# LDR_MODULE.net
KiCad netlist of a schematic drawn in EAGLE
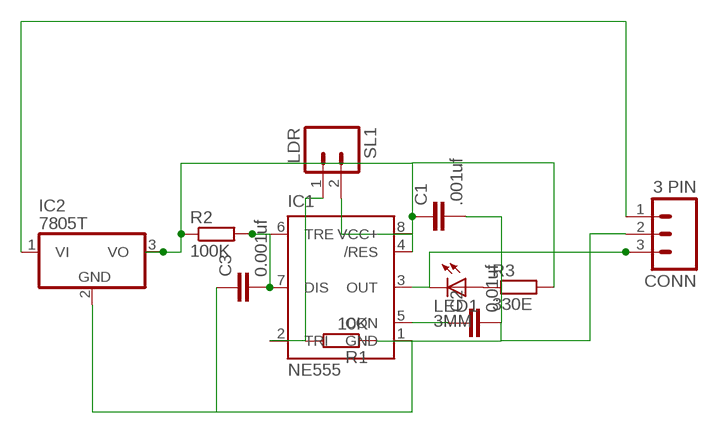
[diagram p0: schematic, sheet 1]

(export (version "E")
  (design (tool "Eeschema 10.0.6"))
  (components
    (comp (ref "C1")
      (value ".001uf")
      (footprint "eagle-import:C2.5-4")
      (libsource (lib "eagle-import") (part "C2.5/4"))
    )
    (comp (ref "C2")
      (value "0.01uf")
      (footprint "eagle-import:C2.5-4")
      (libsource (lib "eagle-import") (part "C2.5/4"))
    )
    (comp (ref "C3")
      (value "0.001uf")
      (footprint "eagle-import:C2.5-4")
      (libsource (lib "eagle-import") (part "C2.5/4"))
    )
    (comp (ref "CONN")
      (value "3 PIN")
      (footprint "eagle-import:03P")
      (libsource (lib "eagle-import") (part "M03"))
    )
    (comp (ref "IC1")
      (value "NE555")
      (footprint "eagle-import:DIL-08")
      (fields (field (name "MF") "Arrow Electronics") (field (name "MPN") "NE555N"))
      (libsource (lib "eagle-import") (part "NE555"))
    )
    (comp (ref "IC2")
      (value "7805T")
      (footprint "eagle-import:TO220H")
      (libsource (lib "eagle-import") (part "78T05"))
    )
    (comp (ref "LED1")
      (value "3MM")
      (footprint "eagle-import:LED3MM")
      (libsource (lib "eagle-import") (part "LED3MM"))
    )
    (comp (ref "R1")
      (value "10K")
      (footprint "eagle-import:0204_7")
      (libsource (lib "eagle-import") (part "R-EU_0204/7"))
    )
    (comp (ref "R2")
      (value "100K")
      (footprint "eagle-import:0204_7")
      (libsource (lib "eagle-import") (part "R-EU_0204/7"))
    )
    (comp (ref "R3")
      (value "330E")
      (footprint "eagle-import:0204_7")
      (libsource (lib "eagle-import") (part "R-EU_0204/7"))
    )
    (comp (ref "SL1")
      (value "LDR")
      (footprint "eagle-import:02P")
      (libsource (lib "eagle-import") (part "M02"))
    )
  )
  (nets
    (net (code "1") (name "Net-(IC1-CON)") (class "Default")
      (node (ref "C2") (pin "1") (pinfunction "1_1") (pintype "passive"))
      (node (ref "IC1") (pin "5") (pinfunction "CON_5") (pintype "input"))
    )
    (net (code "2") (name "Net-(IC1-DIS)") (class "Default")
      (node (ref "C3") (pin "2") (pinfunction "2_2") (pintype "passive"))
      (node (ref "IC1") (pin "6") (pinfunction "TRE_6") (pintype "input"))
      (node (ref "IC1") (pin "7") (pinfunction "DIS_7") (pintype "input"))
      (node (ref "R2") (pin "2") (pinfunction "2_2") (pintype "passive"))
    )
    (net (code "3") (name "Net-(IC1-GND)") (class "Default")
      (node (ref "C1") (pin "2") (pinfunction "2_2") (pintype "passive"))
      (node (ref "C2") (pin "2") (pinfunction "2_2") (pintype "passive"))
      (node (ref "C3") (pin "1") (pinfunction "1_1") (pintype "passive"))
      (node (ref "CONN") (pin "2") (pinfunction "2_2") (pintype "passive"))
      (node (ref "IC1") (pin "1") (pinfunction "GND_1") (pintype "power_in"))
      (node (ref "IC2") (pin "2") (pinfunction "GND_2") (pintype "passive"))
      (node (ref "R1") (pin "1") (pinfunction "1_1") (pintype "passive"))
    )
    (net (code "4") (name "Net-(IC1-OUT)") (class "Default")
      (node (ref "CONN") (pin "3") (pinfunction "3_3") (pintype "passive"))
      (node (ref "IC1") (pin "3") (pinfunction "OUT_3") (pintype "output"))
      (node (ref "LED1") (pin "K") (pinfunction "C_K") (pintype "passive"))
    )
    (net (code "5") (name "Net-(IC1-TRI)") (class "Default")
      (node (ref "IC1") (pin "2") (pinfunction "TRI_2") (pintype "input"))
      (node (ref "R1") (pin "2") (pinfunction "2_2") (pintype "passive"))
      (node (ref "SL1") (pin "1") (pinfunction "1_1") (pintype "passive"))
    )
    (net (code "6") (name "Net-(IC1-VCC+)") (class "Default")
      (node (ref "C1") (pin "1") (pinfunction "1_1") (pintype "passive"))
      (node (ref "IC1") (pin "4") (pinfunction "/RES_4") (pintype "input"))
      (node (ref "IC1") (pin "8") (pinfunction "VCC+_8") (pintype "power_in"))
      (node (ref "IC2") (pin "3") (pinfunction "VO_3") (pintype "passive"))
      (node (ref "R2") (pin "1") (pinfunction "1_1") (pintype "passive"))
      (node (ref "R3") (pin "2") (pinfunction "2_2") (pintype "passive"))
      (node (ref "SL1") (pin "2") (pinfunction "2_2") (pintype "passive"))
    )
    (net (code "7") (name "Net-(IC2-VI)") (class "Default")
      (node (ref "CONN") (pin "1") (pinfunction "1_1") (pintype "passive"))
      (node (ref "IC2") (pin "1") (pinfunction "VI_1") (pintype "input"))
    )
    (net (code "8") (name "Net-(LED1-PadA)") (class "Default")
      (node (ref "LED1") (pin "A") (pinfunction "A_A") (pintype "passive"))
      (node (ref "R3") (pin "1") (pinfunction "1_1") (pintype "passive"))
    )
  )
)
